# ProPrj_ftdi-jtag-xilinx_2025-01-01.net
KiCad netlist of a schematic drawn in EasyEDA Pro
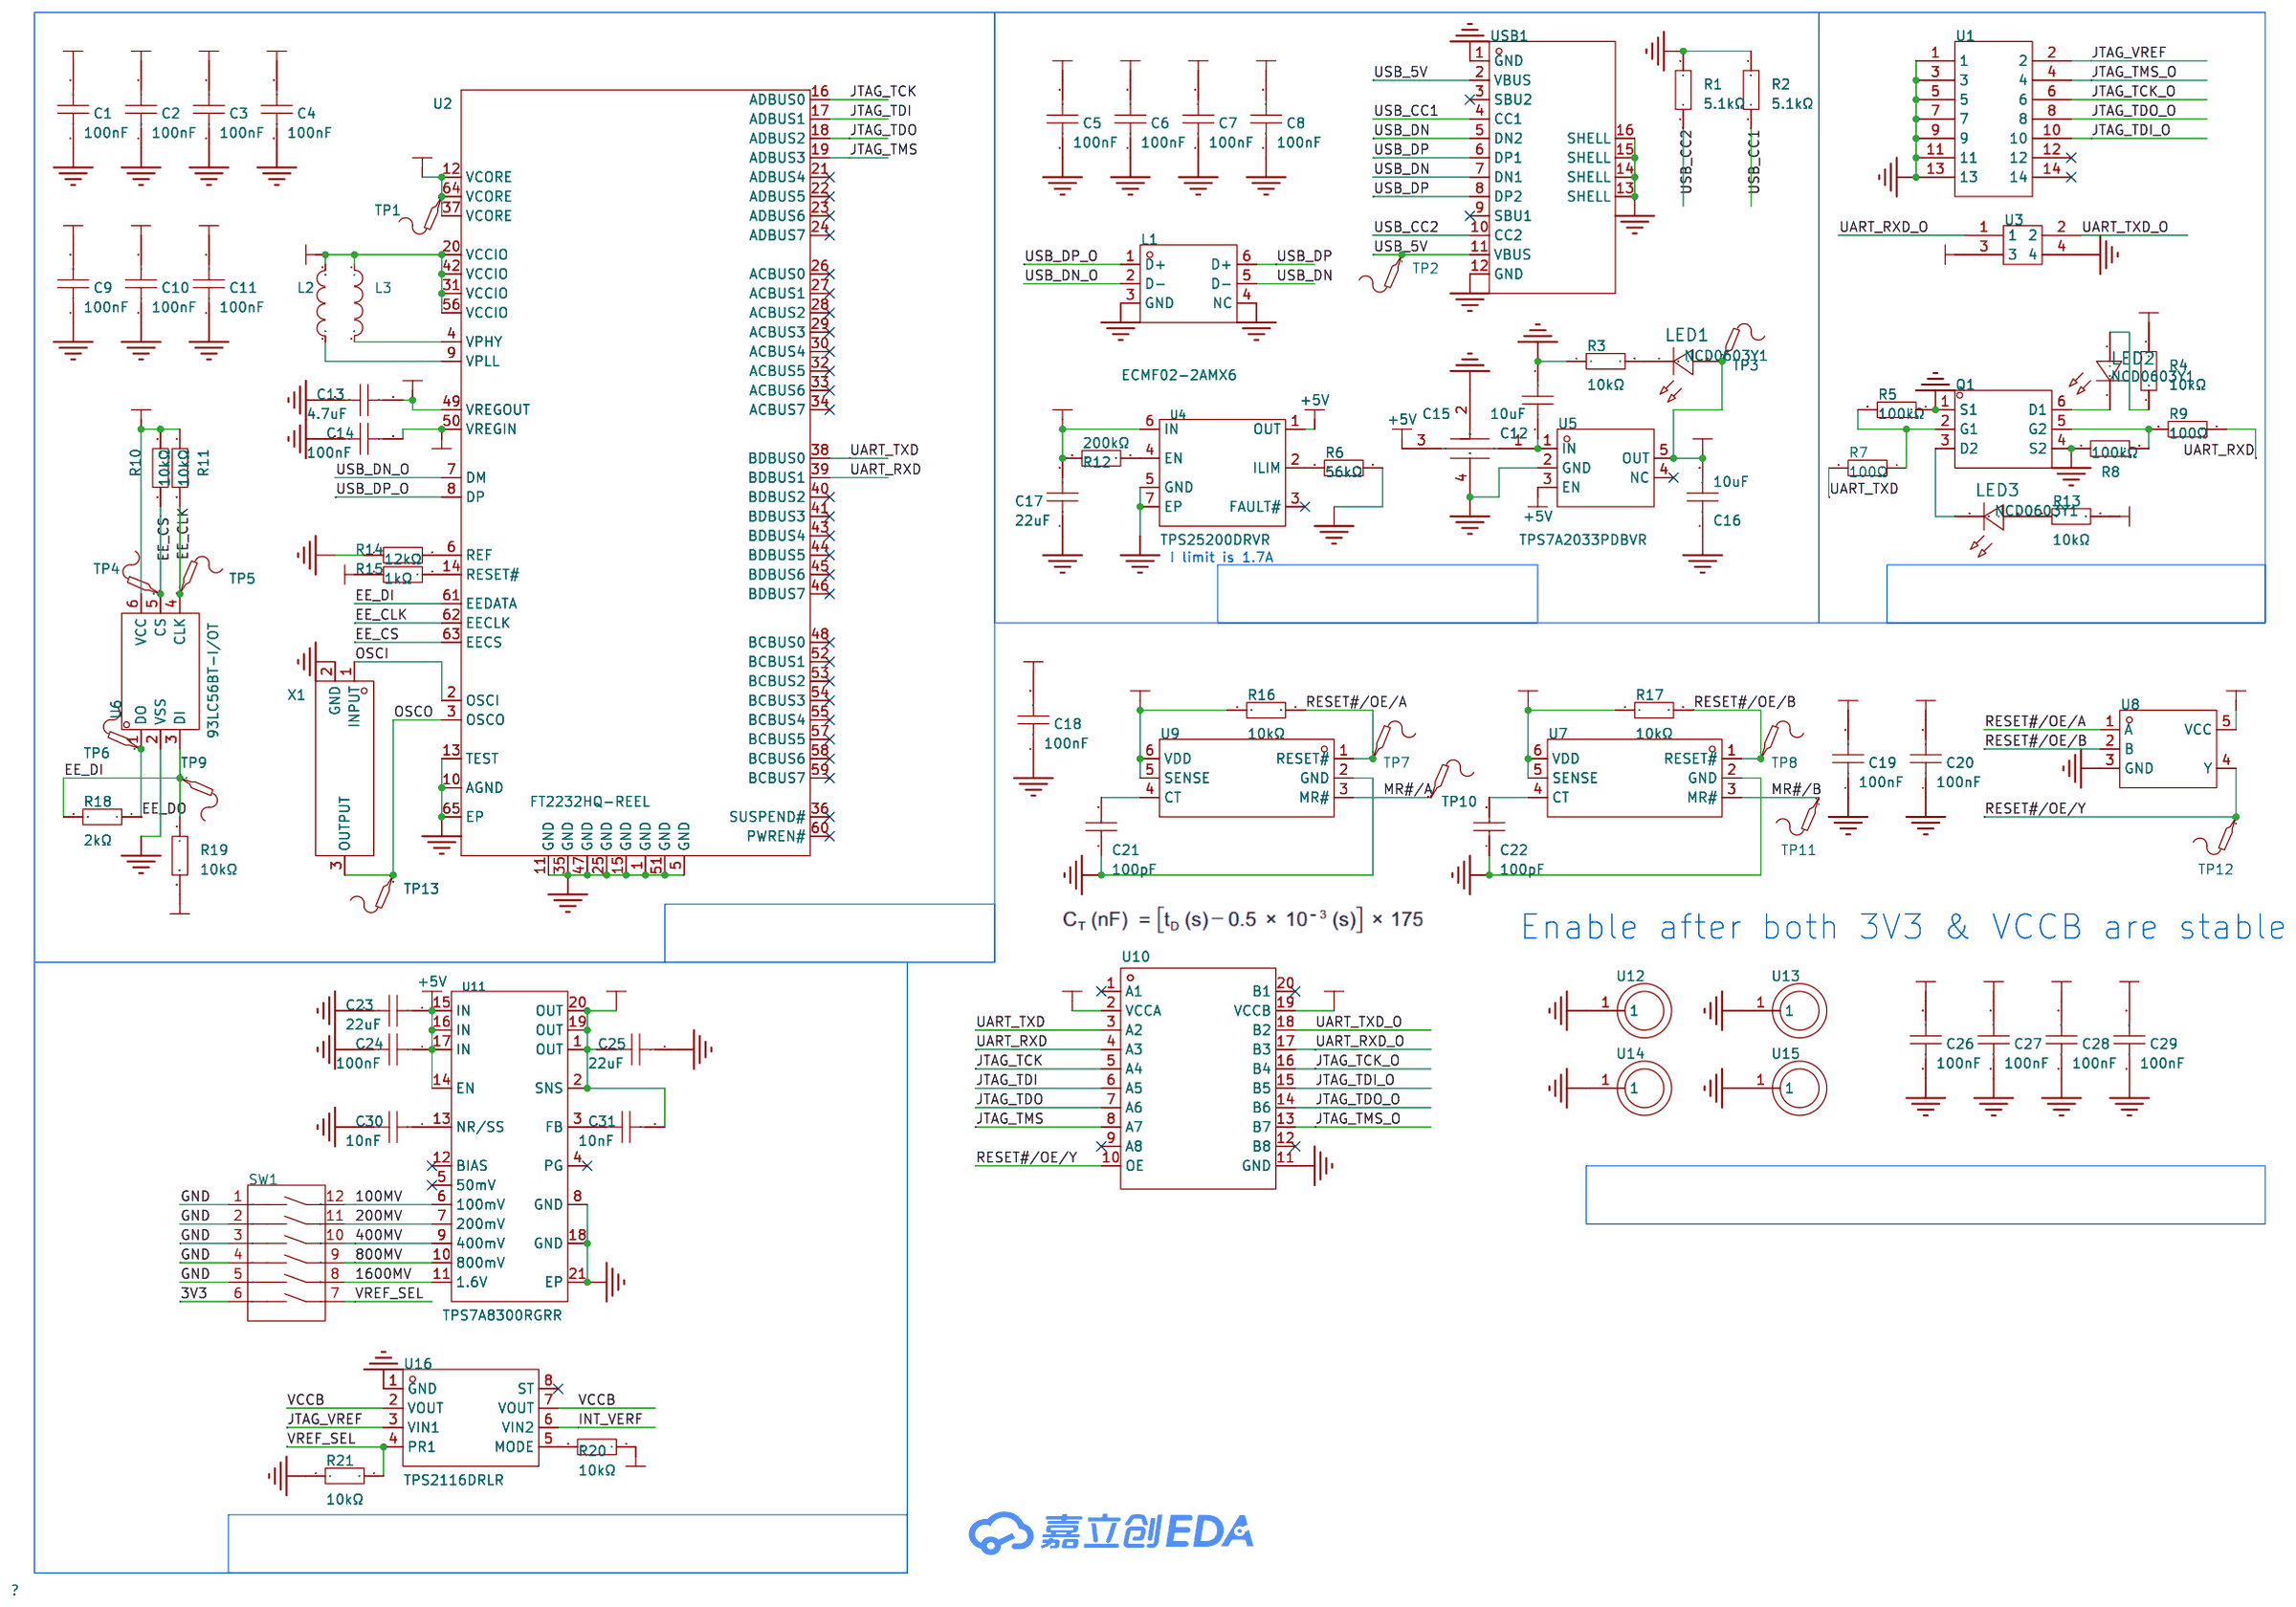
[diagram p0: FT2232HQ]
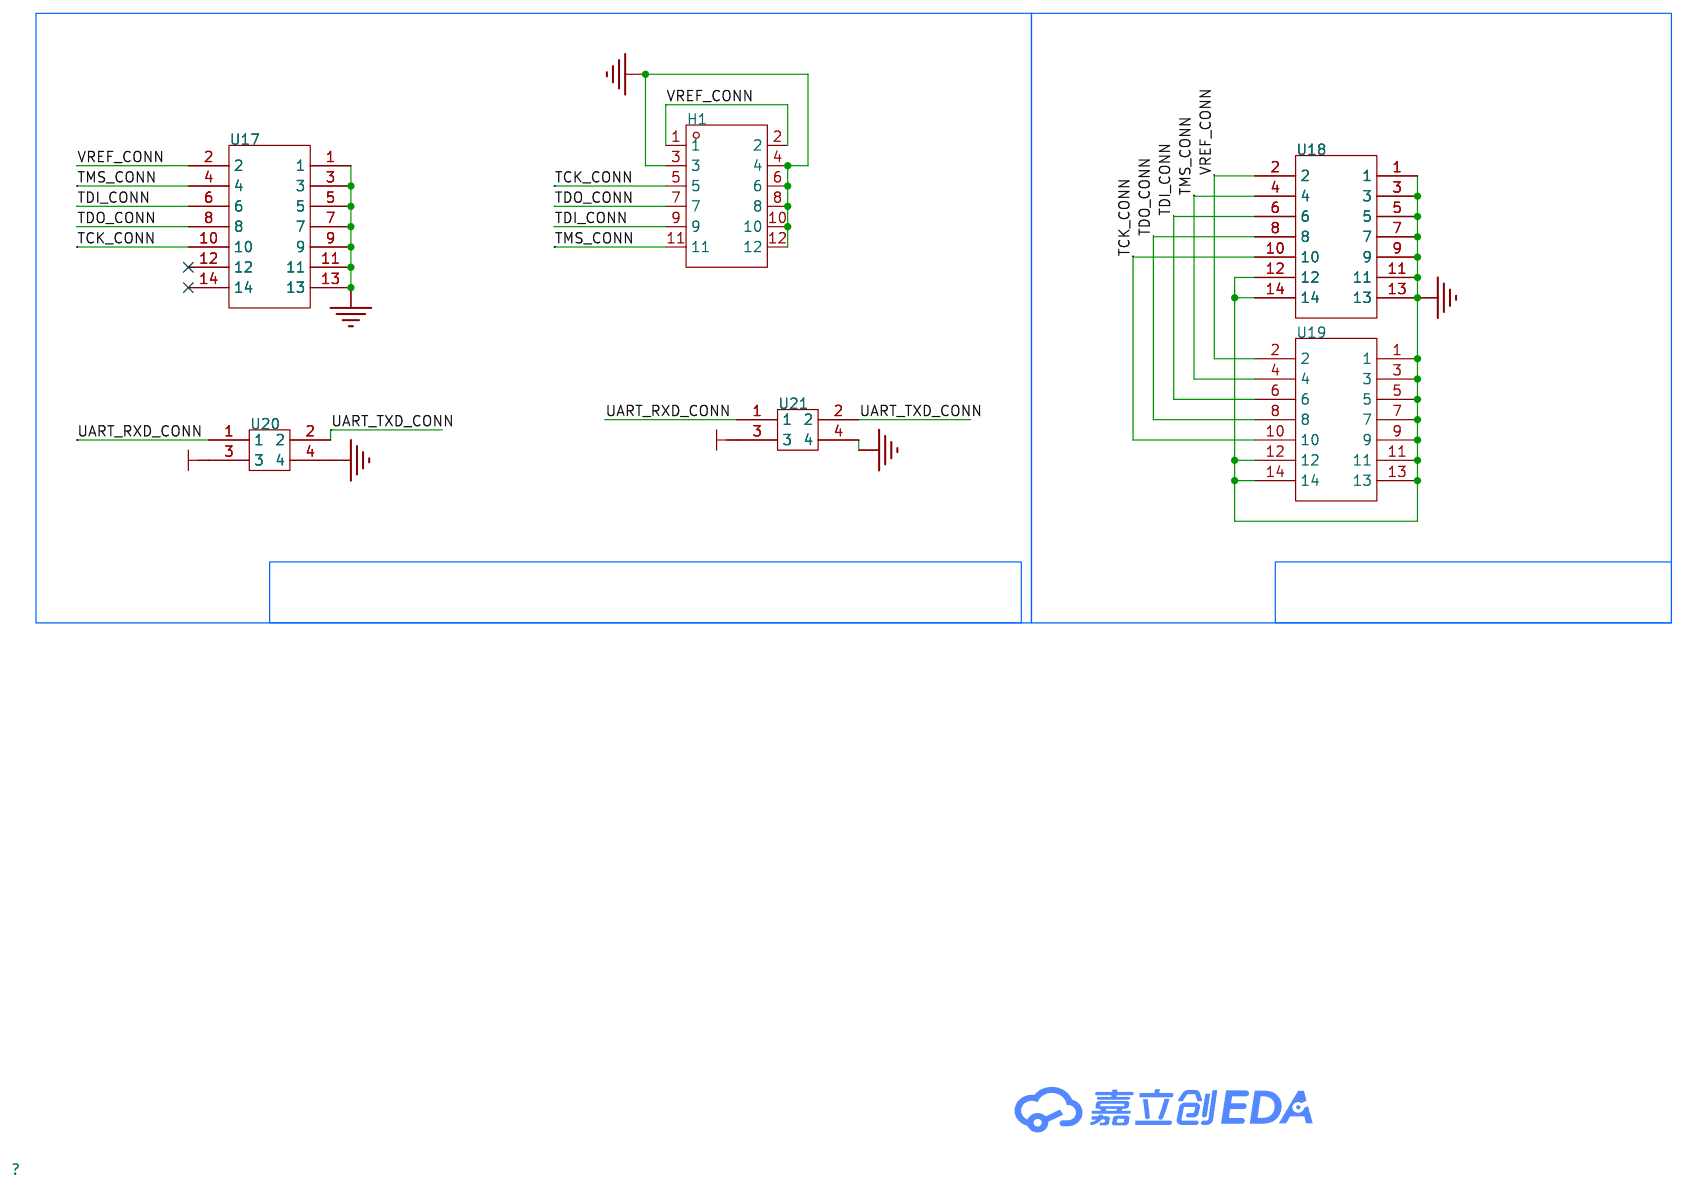
[diagram p1: JTAG Adapter]
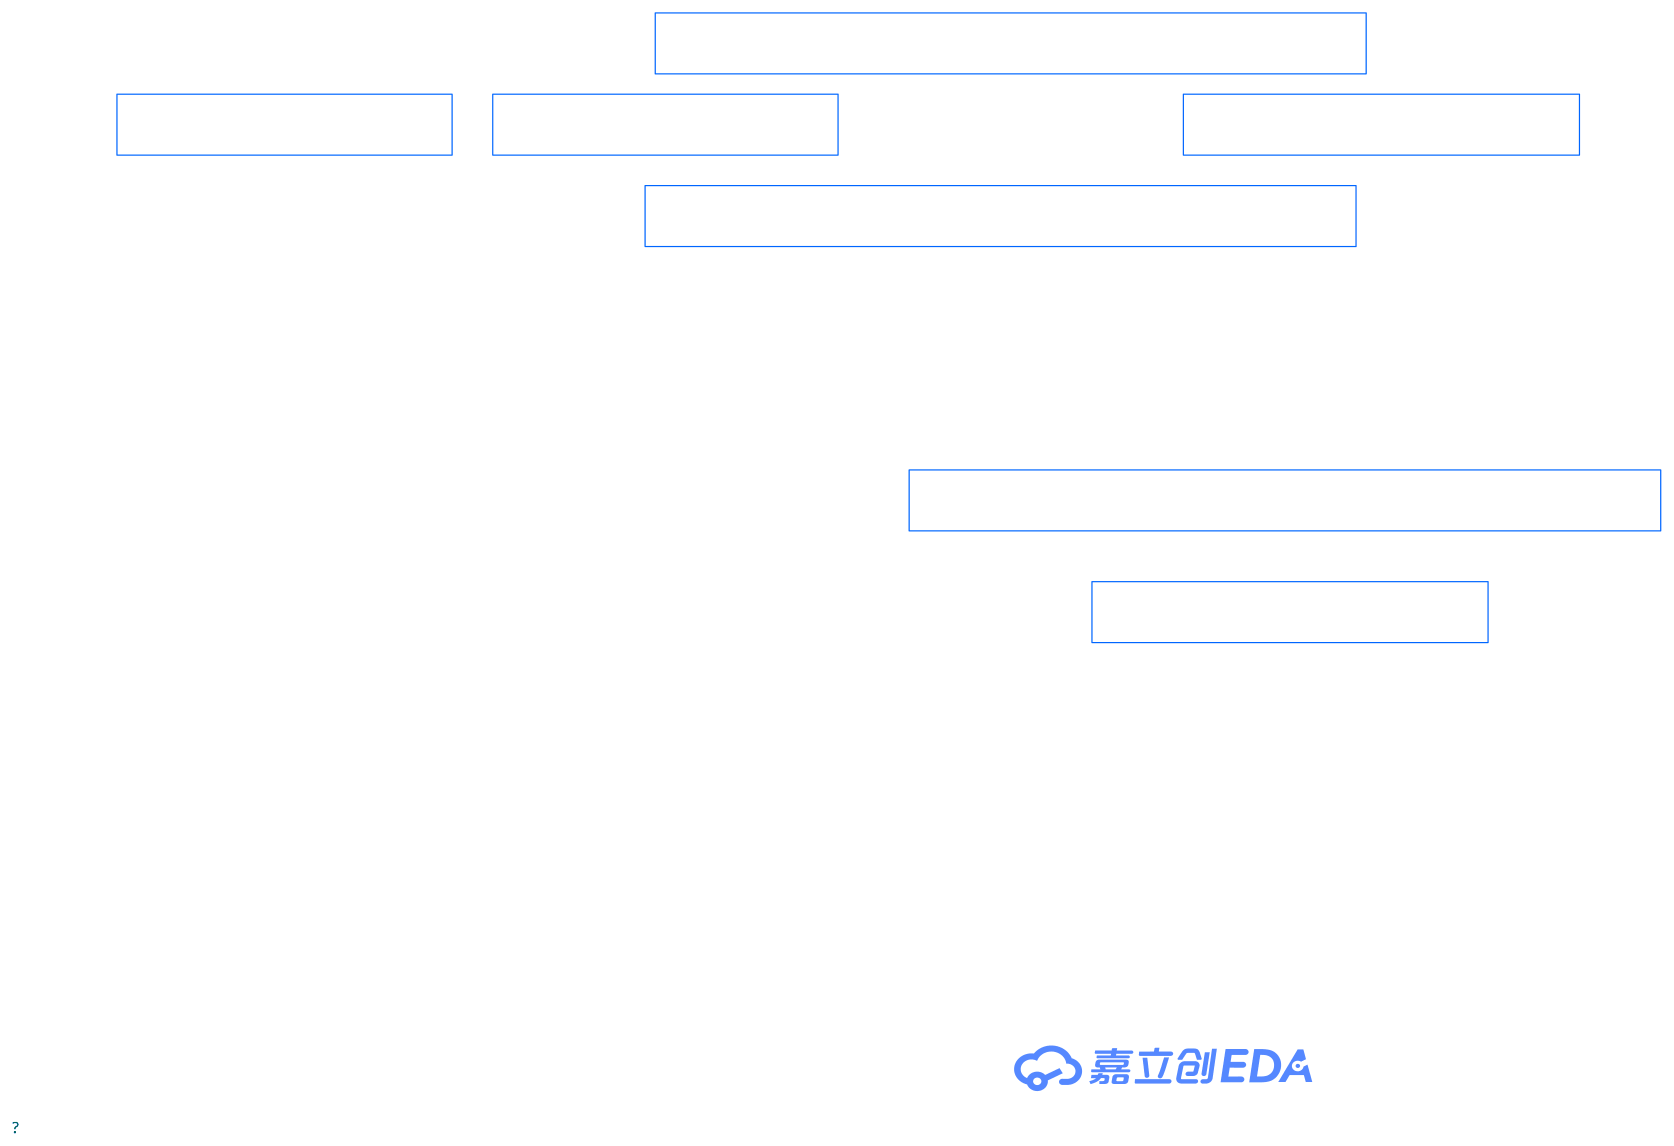
[diagram p2: Overview]

(export (version "E")
  (design (tool "Eeschema 10.0.6"))
  (components
    (comp (ref "C1")
      (value "100nF")
      (footprint "easyedapro:C0603")
      (fields
        (field (name "Manufacturer Part") "CC0402KRX7R7BB104")
        (field (name "Manufacturer") "YAGEO(国巨)")
      )
      (libsource (lib "easyedapro") (part "CapAcitance"))
    )
    (comp (ref "C2")
      (value "100nF")
      (footprint "easyedapro:C0603")
      (fields
        (field (name "Manufacturer Part") "CC0402KRX7R7BB104")
        (field (name "Manufacturer") "YAGEO(国巨)")
      )
      (libsource (lib "easyedapro") (part "CapAcitance"))
    )
    (comp (ref "C3")
      (value "100nF")
      (footprint "easyedapro:C0603")
      (fields
        (field (name "Manufacturer Part") "CC0402KRX7R7BB104")
        (field (name "Manufacturer") "YAGEO(国巨)")
      )
      (libsource (lib "easyedapro") (part "CapAcitance"))
    )
    (comp (ref "C4")
      (value "100nF")
      (footprint "easyedapro:C0603")
      (fields
        (field (name "Manufacturer Part") "CC0402KRX7R7BB104")
        (field (name "Manufacturer") "YAGEO(国巨)")
      )
      (libsource (lib "easyedapro") (part "CapAcitance"))
    )
    (comp (ref "C5")
      (value "100nF")
      (footprint "easyedapro:C0603")
      (fields
        (field (name "Manufacturer Part") "CC0402KRX7R7BB104")
        (field (name "Manufacturer") "YAGEO(国巨)")
      )
      (libsource (lib "easyedapro") (part "CapAcitance"))
    )
    (comp (ref "C6")
      (value "100nF")
      (footprint "easyedapro:C0603")
      (fields
        (field (name "Manufacturer Part") "CC0402KRX7R7BB104")
        (field (name "Manufacturer") "YAGEO(国巨)")
      )
      (libsource (lib "easyedapro") (part "CapAcitance"))
    )
    (comp (ref "C7")
      (value "100nF")
      (footprint "easyedapro:C0603")
      (fields
        (field (name "Manufacturer Part") "CC0402KRX7R7BB104")
        (field (name "Manufacturer") "YAGEO(国巨)")
      )
      (libsource (lib "easyedapro") (part "CapAcitance"))
    )
    (comp (ref "C8")
      (value "100nF")
      (footprint "easyedapro:C0603")
      (fields
        (field (name "Manufacturer Part") "CC0402KRX7R7BB104")
        (field (name "Manufacturer") "YAGEO(国巨)")
      )
      (libsource (lib "easyedapro") (part "CapAcitance"))
    )
    (comp (ref "C9")
      (value "100nF")
      (footprint "easyedapro:C0603")
      (fields
        (field (name "Manufacturer Part") "CC0402KRX7R7BB104")
        (field (name "Manufacturer") "YAGEO(国巨)")
      )
      (libsource (lib "easyedapro") (part "CapAcitance"))
    )
    (comp (ref "C10")
      (value "100nF")
      (footprint "easyedapro:C0603")
      (fields
        (field (name "Manufacturer Part") "CC0402KRX7R7BB104")
        (field (name "Manufacturer") "YAGEO(国巨)")
      )
      (libsource (lib "easyedapro") (part "CapAcitance"))
    )
    (comp (ref "C11")
      (value "100nF")
      (footprint "easyedapro:C0603")
      (fields
        (field (name "Manufacturer Part") "CC0402KRX7R7BB104")
        (field (name "Manufacturer") "YAGEO(国巨)")
      )
      (libsource (lib "easyedapro") (part "CapAcitance"))
    )
    (comp (ref "C12")
      (value "10uF")
      (footprint "easyedapro:C0603")
      (fields
        (field (name "Manufacturer Part") "CL10A106MA8NRNC")
        (field (name "Manufacturer") "SAMSUNG(三星)")
      )
      (libsource (lib "easyedapro") (part "CapAcitance"))
    )
    (comp (ref "C13")
      (value "4.7uF")
      (footprint "easyedapro:C0603")
      (fields
        (field (name "Manufacturer Part") "CL05A475KP5NRNC")
        (field (name "Manufacturer") "SAMSUNG(三星)")
      )
      (libsource (lib "easyedapro") (part "CapAcitance"))
    )
    (comp (ref "C14")
      (value "100nF")
      (footprint "easyedapro:C0603")
      (fields
        (field (name "Manufacturer Part") "CC0402KRX7R7BB104")
        (field (name "Manufacturer") "YAGEO(国巨)")
      )
      (libsource (lib "easyedapro") (part "CapAcitance"))
    )
    (comp (ref "C15")
      (value "NFM21PC104R1E3D")
      (footprint "easyedapro:CAP-SMD_4P-L2.0-W1.25")
      (description "电容量:100nF;精度:±20%;直流电阻:30mΩ;")
      (fields (field (name "Manufacturer") "muRata(村田)"))
      (libsource (lib "easyedapro") (part "NFM21PC104R1E3D"))
    )
    (comp (ref "C16")
      (value "10uF")
      (footprint "easyedapro:C0603")
      (fields
        (field (name "Manufacturer Part") "CL10A106MA8NRNC")
        (field (name "Manufacturer") "SAMSUNG(三星)")
      )
      (libsource (lib "easyedapro") (part "CapAcitance"))
    )
    (comp (ref "C17")
      (value "22uF")
      (footprint "easyedapro:C0603")
      (fields
        (field (name "Manufacturer Part") "CGA0805X5R226M350MT")
        (field (name "Manufacturer") "HRE(芯声)")
      )
      (libsource (lib "easyedapro") (part "CapAcitance"))
    )
    (comp (ref "C18")
      (value "100nF")
      (footprint "easyedapro:C0603")
      (fields
        (field (name "Manufacturer Part") "CC0402KRX7R7BB104")
        (field (name "Manufacturer") "YAGEO(国巨)")
      )
      (libsource (lib "easyedapro") (part "CapAcitance"))
    )
    (comp (ref "C19")
      (value "100nF")
      (footprint "easyedapro:C0603")
      (fields
        (field (name "Manufacturer Part") "CC0402KRX7R7BB104")
        (field (name "Manufacturer") "YAGEO(国巨)")
      )
      (libsource (lib "easyedapro") (part "CapAcitance"))
    )
    (comp (ref "C20")
      (value "100nF")
      (footprint "easyedapro:C0603")
      (fields
        (field (name "Manufacturer Part") "CC0402KRX7R7BB104")
        (field (name "Manufacturer") "YAGEO(国巨)")
      )
      (libsource (lib "easyedapro") (part "CapAcitance"))
    )
    (comp (ref "C21")
      (value "100pF")
      (footprint "easyedapro:C0402")
      (description "容值:100pF;精度:±5%;额定电压:50V;材质(温度系数):NP0;")
      (fields
        (field (name "Manufacturer Part") "CC0402JRNPO9BN101")
        (field (name "Manufacturer") "YAGEO(国巨)")
      )
      (libsource (lib "easyedapro") (part "CC0402JRNPO9BN101"))
    )
    (comp (ref "C22")
      (value "100pF")
      (footprint "easyedapro:C0402")
      (description "容值:100pF;精度:±5%;额定电压:50V;材质(温度系数):NP0;")
      (fields
        (field (name "Manufacturer Part") "CC0402JRNPO9BN101")
        (field (name "Manufacturer") "YAGEO(国巨)")
      )
      (libsource (lib "easyedapro") (part "CC0402JRNPO9BN101"))
    )
    (comp (ref "C23")
      (value "22uF")
      (footprint "easyedapro:C0603")
      (fields
        (field (name "Manufacturer Part") "CGA0805X5R226M350MT")
        (field (name "Manufacturer") "HRE(芯声)")
      )
      (libsource (lib "easyedapro") (part "CapAcitance"))
    )
    (comp (ref "C24")
      (value "100nF")
      (footprint "easyedapro:C0603")
      (fields
        (field (name "Manufacturer Part") "CC0402KRX7R7BB104")
        (field (name "Manufacturer") "YAGEO(国巨)")
      )
      (libsource (lib "easyedapro") (part "CapAcitance"))
    )
    (comp (ref "C25")
      (value "22uF")
      (footprint "easyedapro:C0603")
      (fields
        (field (name "Manufacturer Part") "CGA0805X5R226M350MT")
        (field (name "Manufacturer") "HRE(芯声)")
      )
      (libsource (lib "easyedapro") (part "CapAcitance"))
    )
    (comp (ref "C26")
      (value "100nF")
      (footprint "easyedapro:C0603")
      (fields
        (field (name "Manufacturer Part") "CC0402KRX7R7BB104")
        (field (name "Manufacturer") "YAGEO(国巨)")
      )
      (libsource (lib "easyedapro") (part "CapAcitance"))
    )
    (comp (ref "C27")
      (value "100nF")
      (footprint "easyedapro:C0603")
      (fields
        (field (name "Manufacturer Part") "CC0402KRX7R7BB104")
        (field (name "Manufacturer") "YAGEO(国巨)")
      )
      (libsource (lib "easyedapro") (part "CapAcitance"))
    )
    (comp (ref "C28")
      (value "100nF")
      (footprint "easyedapro:C0603")
      (fields
        (field (name "Manufacturer Part") "CC0402KRX7R7BB104")
        (field (name "Manufacturer") "YAGEO(国巨)")
      )
      (libsource (lib "easyedapro") (part "CapAcitance"))
    )
    (comp (ref "C29")
      (value "100nF")
      (footprint "easyedapro:C0603")
      (fields
        (field (name "Manufacturer Part") "CC0402KRX7R7BB104")
        (field (name "Manufacturer") "YAGEO(国巨)")
      )
      (libsource (lib "easyedapro") (part "CapAcitance"))
    )
    (comp (ref "C30")
      (value "10nF")
      (footprint "easyedapro:C0603")
      (fields
        (field (name "Manufacturer Part") "CC0402KRX7R9BB103")
        (field (name "Manufacturer") "YAGEO(国巨)")
      )
      (libsource (lib "easyedapro") (part "CapAcitance"))
    )
    (comp (ref "C31")
      (value "10nF")
      (footprint "easyedapro:C0603")
      (fields
        (field (name "Manufacturer Part") "CC0402KRX7R9BB103")
        (field (name "Manufacturer") "YAGEO(国巨)")
      )
      (libsource (lib "easyedapro") (part "CapAcitance"))
    )
    (comp (ref "L1")
      (value "ECMF02-2AMX6")
      (footprint "easyedapro:UFQFN-6_L1.7-W1.5")
      (description "线路数:2;直流电阻(DCR):2.5Ω;")
      (fields (field (name "Manufacturer") "ST(意法半导体)"))
      (libsource (lib "easyedapro") (part "ECMF02-2AMX6"))
    )
    (comp (ref "L2")
      (value "BLM15PD121SN1D")
      (footprint "easyedapro:L0402")
      (description "标称阻抗@测试频率:120Ω@100MHz;误差:±25%;直流电阻(RDC):90mΩ;")
      (fields (field (name "Manufacturer") "muRata(村田)"))
      (libsource (lib "easyedapro") (part "BLM15PD121SN1D"))
    )
    (comp (ref "L3")
      (value "BLM15PD121SN1D")
      (footprint "easyedapro:L0402")
      (description "标称阻抗@测试频率:120Ω@100MHz;误差:±25%;直流电阻(RDC):90mΩ;")
      (fields (field (name "Manufacturer") "muRata(村田)"))
      (libsource (lib "easyedapro") (part "BLM15PD121SN1D"))
    )
    (comp (ref "LED1")
      (value "NCD0603Y1")
      (footprint "easyedapro:LED_0603")
      (fields (field (name "Manufacturer") "国星光电"))
      (libsource (lib "easyedapro") (part "LED_R"))
    )
    (comp (ref "LED2")
      (value "NCD0603Y1")
      (footprint "easyedapro:LED_0603")
      (fields (field (name "Manufacturer") "国星光电"))
      (libsource (lib "easyedapro") (part "LED_R"))
    )
    (comp (ref "LED3")
      (value "NCD0603Y1")
      (footprint "easyedapro:LED_0603")
      (fields (field (name "Manufacturer") "国星光电"))
      (libsource (lib "easyedapro") (part "LED_R"))
    )
    (comp (ref "Q1")
      (value "BSS138PS,115")
      (footprint "easyedapro:SOT-363_L2.0-W1.3-P0.65-LS2.1-BR")
      (fields (field (name "Manufacturer") "Nexperia(安世)"))
      (libsource (lib "easyedapro") (part "BSS138PS,115"))
    )
    (comp (ref "R1")
      (value "5.1kΩ")
      (footprint "easyedapro:R0603")
      (fields
        (field (name "Manufacturer Part") "0402WGF5101TCE")
        (field (name "Manufacturer") "UNI-ROYAL(厚声)")
      )
      (libsource (lib "easyedapro") (part "电阻"))
    )
    (comp (ref "R2")
      (value "5.1kΩ")
      (footprint "easyedapro:R0603")
      (fields
        (field (name "Manufacturer Part") "0402WGF5101TCE")
        (field (name "Manufacturer") "UNI-ROYAL(厚声)")
      )
      (libsource (lib "easyedapro") (part "电阻"))
    )
    (comp (ref "R3")
      (value "10kΩ")
      (footprint "easyedapro:R0603")
      (fields (field (name "Manufacturer Part") "RC0402FR-0710KL") (field (name "Manufacturer") "YAGEO(国巨)"))
      (libsource (lib "easyedapro") (part "电阻"))
    )
    (comp (ref "R4")
      (value "10kΩ")
      (footprint "easyedapro:R0603")
      (fields (field (name "Manufacturer Part") "RC0402FR-0710KL") (field (name "Manufacturer") "YAGEO(国巨)"))
      (libsource (lib "easyedapro") (part "电阻"))
    )
    (comp (ref "R5")
      (value "100kΩ")
      (footprint "easyedapro:R0603")
      (fields (field (name "Manufacturer Part") "RC0402FR-07100KL") (field (name "Manufacturer") "YAGEO(国巨)"))
      (libsource (lib "easyedapro") (part "电阻"))
    )
    (comp (ref "R6")
      (value "56kΩ")
      (footprint "easyedapro:R0603")
      (fields
        (field (name "Manufacturer Part") "0402WGF5602TCE")
        (field (name "Manufacturer") "UNI-ROYAL(厚声)")
      )
      (libsource (lib "easyedapro") (part "电阻"))
    )
    (comp (ref "R7")
      (value "100Ω")
      (footprint "easyedapro:R0603")
      (fields
        (field (name "Manufacturer Part") "0402WGF1000TCE")
        (field (name "Manufacturer") "UNI-ROYAL(厚声)")
      )
      (libsource (lib "easyedapro") (part "电阻"))
    )
    (comp (ref "R8")
      (value "100kΩ")
      (footprint "easyedapro:R0603")
      (fields (field (name "Manufacturer Part") "RC0402FR-07100KL") (field (name "Manufacturer") "YAGEO(国巨)"))
      (libsource (lib "easyedapro") (part "电阻"))
    )
    (comp (ref "R9")
      (value "100Ω")
      (footprint "easyedapro:R0603")
      (fields
        (field (name "Manufacturer Part") "0402WGF1000TCE")
        (field (name "Manufacturer") "UNI-ROYAL(厚声)")
      )
      (libsource (lib "easyedapro") (part "电阻"))
    )
    (comp (ref "R10")
      (value "10kΩ")
      (footprint "easyedapro:R0603")
      (fields (field (name "Manufacturer Part") "RC0402FR-0710KL") (field (name "Manufacturer") "YAGEO(国巨)"))
      (libsource (lib "easyedapro") (part "电阻"))
    )
    (comp (ref "R11")
      (value "10kΩ")
      (footprint "easyedapro:R0603")
      (fields (field (name "Manufacturer Part") "RC0402FR-0710KL") (field (name "Manufacturer") "YAGEO(国巨)"))
      (libsource (lib "easyedapro") (part "电阻"))
    )
    (comp (ref "R12")
      (value "200kΩ")
      (footprint "easyedapro:R0603")
      (fields
        (field (name "Manufacturer Part") "0402WGF2003TCE")
        (field (name "Manufacturer") "UNI-ROYAL(厚声)")
      )
      (libsource (lib "easyedapro") (part "电阻"))
    )
    (comp (ref "R13")
      (value "10kΩ")
      (footprint "easyedapro:R0603")
      (fields (field (name "Manufacturer Part") "RC0402FR-0710KL") (field (name "Manufacturer") "YAGEO(国巨)"))
      (libsource (lib "easyedapro") (part "电阻"))
    )
    (comp (ref "R14")
      (value "12kΩ")
      (footprint "easyedapro:R0603")
      (fields
        (field (name "Manufacturer Part") "0402WGF1202TCE")
        (field (name "Manufacturer") "UNI-ROYAL(厚声)")
      )
      (libsource (lib "easyedapro") (part "电阻"))
    )
    (comp (ref "R15")
      (value "1kΩ")
      (footprint "easyedapro:R0603")
      (fields
        (field (name "Manufacturer Part") "0402WGF1001TCE")
        (field (name "Manufacturer") "UNI-ROYAL(厚声)")
      )
      (libsource (lib "easyedapro") (part "电阻"))
    )
    (comp (ref "R16")
      (value "10kΩ")
      (footprint "easyedapro:R0603")
      (fields (field (name "Manufacturer Part") "RC0402FR-0710KL") (field (name "Manufacturer") "YAGEO(国巨)"))
      (libsource (lib "easyedapro") (part "电阻"))
    )
    (comp (ref "R17")
      (value "10kΩ")
      (footprint "easyedapro:R0603")
      (fields (field (name "Manufacturer Part") "RC0402FR-0710KL") (field (name "Manufacturer") "YAGEO(国巨)"))
      (libsource (lib "easyedapro") (part "电阻"))
    )
    (comp (ref "R18")
      (value "2kΩ")
      (footprint "easyedapro:R0603")
      (fields (field (name "Manufacturer Part") "FRC0402F2001TS") (field (name "Manufacturer") "FOJAN(富捷)"))
      (libsource (lib "easyedapro") (part "电阻"))
    )
    (comp (ref "R19")
      (value "10kΩ")
      (footprint "easyedapro:R0603")
      (fields (field (name "Manufacturer Part") "RC0402FR-0710KL") (field (name "Manufacturer") "YAGEO(国巨)"))
      (libsource (lib "easyedapro") (part "电阻"))
    )
    (comp (ref "R20")
      (value "10kΩ")
      (footprint "easyedapro:R0603")
      (fields (field (name "Manufacturer Part") "RC0402FR-0710KL") (field (name "Manufacturer") "YAGEO(国巨)"))
      (libsource (lib "easyedapro") (part "电阻"))
    )
    (comp (ref "R21")
      (value "10kΩ")
      (footprint "easyedapro:R0603")
      (fields (field (name "Manufacturer Part") "RC0402FR-0710KL") (field (name "Manufacturer") "YAGEO(国巨)"))
      (libsource (lib "easyedapro") (part "电阻"))
    )
    (comp (ref "SW1")
      (value "SMQP-06B-TP")
      (footprint "easyedapro:SW-TH_12P-P2.54_SMQP-06B-TP")
      (description "类型:琴键;电路结构:-;开关位数:6位;额定电流:25mA;额定电压:24V;使用寿命:5千次;颜色:蓝色;")
      (fields (field (name "Manufacturer") "SM Switch"))
      (libsource (lib "easyedapro") (part "SMQP-06B-TP"))
    )
    (comp (ref "TP1")
      (value "~")
      (footprint "easyedapro:Test-Point-0.5mm")
      (description "Test Point 测试点")
      (libsource (lib "easyedapro") (part "Test-Point"))
    )
    (comp (ref "TP2")
      (value "~")
      (footprint "easyedapro:Test-Point-0.5mm")
      (description "Test Point 测试点")
      (libsource (lib "easyedapro") (part "Test-Point"))
    )
    (comp (ref "TP3")
      (value "~")
      (footprint "easyedapro:Test-Point-0.5mm")
      (description "Test Point 测试点")
      (libsource (lib "easyedapro") (part "Test-Point"))
    )
    (comp (ref "TP4")
      (value "~")
      (footprint "easyedapro:Test-Point-0.5mm")
      (description "Test Point 测试点")
      (libsource (lib "easyedapro") (part "Test-Point"))
    )
    (comp (ref "TP5")
      (value "~")
      (footprint "easyedapro:Test-Point-0.5mm")
      (description "Test Point 测试点")
      (libsource (lib "easyedapro") (part "Test-Point"))
    )
    (comp (ref "TP6")
      (value "~")
      (footprint "easyedapro:Test-Point-0.5mm")
      (description "Test Point 测试点")
      (libsource (lib "easyedapro") (part "Test-Point"))
    )
    (comp (ref "TP7")
      (value "~")
      (footprint "easyedapro:Test-Point-0.5mm")
      (description "Test Point 测试点")
      (libsource (lib "easyedapro") (part "Test-Point"))
    )
    (comp (ref "TP8")
      (value "~")
      (footprint "easyedapro:Test-Point-0.5mm")
      (description "Test Point 测试点")
      (libsource (lib "easyedapro") (part "Test-Point"))
    )
    (comp (ref "TP9")
      (value "~")
      (footprint "easyedapro:Test-Point-0.5mm")
      (description "Test Point 测试点")
      (libsource (lib "easyedapro") (part "Test-Point"))
    )
    (comp (ref "TP10")
      (value "~")
      (footprint "easyedapro:Test-Point-0.5mm")
      (description "Test Point 测试点")
      (libsource (lib "easyedapro") (part "Test-Point"))
    )
    (comp (ref "TP11")
      (value "~")
      (footprint "easyedapro:Test-Point-0.5mm")
      (description "Test Point 测试点")
      (libsource (lib "easyedapro") (part "Test-Point"))
    )
    (comp (ref "TP12")
      (value "~")
      (footprint "easyedapro:Test-Point-0.5mm")
      (description "Test Point 测试点")
      (libsource (lib "easyedapro") (part "Test-Point"))
    )
    (comp (ref "TP13")
      (value "~")
      (footprint "easyedapro:Test-Point-0.5mm")
      (description "Test Point 测试点")
      (libsource (lib "easyedapro") (part "Test-Point"))
    )
    (comp (ref "U1")
      (value "~")
      (footprint "easyedapro:JTAG_V3")
      (libsource (lib "easyedapro") (part "jtagv4"))
    )
    (comp (ref "U2")
      (value "FT2232HQ-REEL")
      (footprint "easyedapro:QFN-64_L9.0-W9.0-P0.50-TL-EP4.3")
      (description "应用功能:USB转UART；USB转FIFO;接口协议:UART;供电电压:3V~3.6V;")
      (fields (field (name "Manufacturer") "FTDI(飞特帝亚)"))
      (libsource (lib "easyedapro") (part "FT2232HQ-REEL"))
    )
    (comp (ref "U3") (value "~") (footprint "easyedapro:2x2p侧贴排针") (libsource (lib "easyedapro") (part "2")))
    (comp (ref "U4")
      (value "TPS25200DRVR")
      (footprint "easyedapro:WSON-6_L2.0-W2.0-P0.65-TL-EP")
      (description "TPS25200 具有过压钳位的 6.5V/2.8A 电子保险丝")
      (fields (field (name "Manufacturer") "TI(德州仪器)"))
      (libsource (lib "easyedapro") (part "TPS25200DRVR"))
    )
    (comp (ref "U5")
      (value "TPS7A2033PDBVR")
      (footprint "easyedapro:SOT-23-5_L2.9-W1.6-P0.95-LS2.8-BR")
      (fields (field (name "Manufacturer") "TI(德州仪器)"))
      (libsource (lib "easyedapro") (part "TPS7A2033PDBVR"))
    )
    (comp (ref "U6")
      (value "93LC56BT-I/OT")
      (footprint "easyedapro:SOT-23-6_L2.9-W1.6-P0.95-LS2.8-BR")
      (fields (field (name "Manufacturer") "MICROCHIP(美国微芯)"))
      (libsource (lib "easyedapro") (part "93LC56BT-I/OT"))
    )
    (comp (ref "U7")
      (value "TPS3808G33DBVR")
      (footprint "easyedapro:SOT-23-6_L2.9-W1.6-P0.95-LS2.8-BR")
      (description "复位有效电平:低电平有效;受监控电压数:1;复位超时:-;")
      (fields (field (name "Manufacturer") "TI(德州仪器)"))
      (libsource (lib "easyedapro") (part "TPS3808G33DBVR"))
    )
    (comp (ref "U8")
      (value "SN74LVC1G08DBVR")
      (footprint "easyedapro:TSOT-23-5_L2.9-W1.6-P0.95-LS2.8-BR")
      (description "逻辑类型:与门;通道数:1;电源电压:1.65V~5.5V;静态电流(最大值):10uA;最大传播延迟:10ns@5V,15pF;")
      (fields (field (name "Manufacturer") "UMW(友台半导体)"))
      (libsource (lib "easyedapro") (part "SN74LVC1G08DBVR_C434068"))
    )
    (comp (ref "U9")
      (value "TPS3808G33DBVR")
      (footprint "easyedapro:SOT-23-6_L2.9-W1.6-P0.95-LS2.8-BR")
      (description "复位有效电平:低电平有效;受监控电压数:1;复位超时:-;")
      (fields (field (name "Manufacturer") "TI(德州仪器)"))
      (libsource (lib "easyedapro") (part "TPS3808G33DBVR"))
    )
    (comp (ref "U10")
      (value "TXB0108PWR")
      (footprint "easyedapro:TSSOP-20_L6.5-W4.4-P0.65-LS6.4-BL")
      (description "数据速率:100Mbps;电压(VCCA):1.2V~3.6V;电压(VCCB):1.65V~5.5V;电路数:1;每个电路通道数:8;")
      (fields (field (name "Manufacturer") "TI(德州仪器)"))
      (libsource (lib "easyedapro") (part "TXB0108PWR"))
    )
    (comp (ref "U11")
      (value "TPS7A8300RGRR")
      (footprint "easyedapro:VQFN-20_L3.5-W3.5-P0.50-BL-EP2.0")
      (description "输出类型:-;")
      (fields (field (name "Manufacturer") "TI(德州仪器)"))
      (libsource (lib "easyedapro") (part "TPS7A8300RGRR"))
    )
    (comp (ref "U12")
      (value "~")
      (footprint "easyedapro:M2焊接螺柱")
      (libsource (lib "easyedapro") (part "M2焊接螺柱"))
    )
    (comp (ref "U13")
      (value "~")
      (footprint "easyedapro:M2焊接螺柱")
      (libsource (lib "easyedapro") (part "M2焊接螺柱"))
    )
    (comp (ref "U14")
      (value "~")
      (footprint "easyedapro:M2焊接螺柱")
      (libsource (lib "easyedapro") (part "M2焊接螺柱"))
    )
    (comp (ref "U15")
      (value "~")
      (footprint "easyedapro:M2焊接螺柱")
      (libsource (lib "easyedapro") (part "M2焊接螺柱"))
    )
    (comp (ref "U16")
      (value "TPS2116DRLR")
      (footprint "easyedapro:SOT-583-8_L2.1-W1.6-P0.50-LS1.6-BL")
      (description "通道数:1;输出电流:2.5A;输入电压:1.6V~5.5V;导通电阻:42mΩ;")
      (fields (field (name "Manufacturer") "TI(德州仪器)"))
      (libsource (lib "easyedapro") (part "TPS2116DRLR"))
    )
    (comp (ref "USB1")
      (value "TYPEC-302-BRP16SC16")
      (footprint "easyedapro:USB-C-SMD_TYPEC-302-BRP16SC16")
      (fields (field (name "Manufacturer") "XUNPU(讯普)"))
      (libsource (lib "easyedapro") (part "TYPEC-302-BRP16SC16"))
    )
    (comp (ref "X1")
      (value "12MHz")
      (footprint "easyedapro:CRYSTAL-SMD_3P-L3.2-W1.3-P1.2-BL")
      (description "频率:12MHz;内置负载电容:10pF;谐振阻抗:30Ω;")
      (fields
        (field (name "Manufacturer Part") "CSTNE12M0G52A000R0")
        (field (name "Manufacturer") "muRata(村田)")
      )
      (libsource (lib "easyedapro") (part "CSTNE12M0G52A000R0"))
    )
    (comp (ref "H1")
      (value "PZ2.54-2x6-11.2")
      (footprint "easyedapro:HDR-TH_12P-P2.54-V-M-R2-C6-S2.54")
      (fields (field (name "Manufacturer") "ZHOURI(洲日)"))
      (libsource (lib "easyedapro") (part "PZ2.54-2X6-11.2"))
    )
    (comp (ref "U17")
      (value "~")
      (footprint "easyedapro:JTAG_V3")
      (libsource (lib "easyedapro") (part "jtagv4"))
    )
    (comp (ref "U18")
      (value "~")
      (footprint "easyedapro:JTAG_V3")
      (libsource (lib "easyedapro") (part "jtagv4"))
    )
    (comp (ref "U19")
      (value "~")
      (footprint "easyedapro:JTAG_V3")
      (libsource (lib "easyedapro") (part "jtagv4"))
    )
    (comp (ref "U20") (value "~") (footprint "easyedapro:2x2p侧贴排针") (libsource (lib "easyedapro") (part "2")))
    (comp (ref "U21") (value "~") (footprint "easyedapro:2x2p侧贴排针") (libsource (lib "easyedapro") (part "2")))
  )
  (nets
    (net (code "1") (name "+5V") (class "Default")
      (node (ref "C15") (pin "3") (pinfunction "OUT_3") (pintype "input"))
      (node (ref "C23") (pin "2") (pinfunction "2_2") (pintype "input"))
      (node (ref "C24") (pin "1") (pinfunction "1_1") (pintype "input"))
      (node (ref "U11") (pin "14") (pinfunction "EN_14") (pintype "input"))
      (node (ref "U11") (pin "15") (pinfunction "IN_15") (pintype "input"))
      (node (ref "U11") (pin "16") (pinfunction "IN_16") (pintype "input"))
      (node (ref "U11") (pin "17") (pinfunction "IN_17") (pintype "input"))
      (node (ref "U4") (pin "1") (pinfunction "OUT_1") (pintype "input"))
      (node (ref "U5") (pin "3") (pinfunction "EN_3") (pintype "input"))
    )
    (net (code "2") (name "3V3") (class "Default")
      (node (ref "C1") (pin "2") (pinfunction "2_2") (pintype "input"))
      (node (ref "C14") (pin "2") (pinfunction "2_2") (pintype "input"))
      (node (ref "C16") (pin "2") (pinfunction "2_2") (pintype "input"))
      (node (ref "C18") (pin "2") (pinfunction "2_2") (pintype "input"))
      (node (ref "C2") (pin "2") (pinfunction "2_2") (pintype "input"))
      (node (ref "C20") (pin "2") (pinfunction "2_2") (pintype "input"))
      (node (ref "C26") (pin "2") (pinfunction "2_2") (pintype "input"))
      (node (ref "C27") (pin "2") (pinfunction "2_2") (pintype "input"))
      (node (ref "C3") (pin "2") (pinfunction "2_2") (pintype "input"))
      (node (ref "C4") (pin "2") (pinfunction "2_2") (pintype "input"))
      (node (ref "C5") (pin "2") (pinfunction "2_2") (pintype "input"))
      (node (ref "C6") (pin "2") (pinfunction "2_2") (pintype "input"))
      (node (ref "C7") (pin "2") (pinfunction "2_2") (pintype "input"))
      (node (ref "C8") (pin "2") (pinfunction "2_2") (pintype "input"))
      (node (ref "L2") (pin "2") (pinfunction "2_2") (pintype "input"))
      (node (ref "L3") (pin "1") (pinfunction "1_1") (pintype "input"))
      (node (ref "LED1") (pin "2") (pinfunction "A_2") (pintype "input"))
      (node (ref "R10") (pin "1") (pinfunction "1_1") (pintype "input"))
      (node (ref "R11") (pin "1") (pinfunction "1_1") (pintype "input"))
      (node (ref "R13") (pin "1") (pinfunction "1_1") (pintype "input"))
      (node (ref "R15") (pin "1") (pinfunction "1_1") (pintype "input"))
      (node (ref "R16") (pin "1") (pinfunction "1_1") (pintype "input"))
      (node (ref "R19") (pin "2") (pinfunction "2_2") (pintype "input"))
      (node (ref "R20") (pin "1") (pinfunction "1_1") (pintype "input"))
      (node (ref "R4") (pin "2") (pinfunction "2_2") (pintype "input"))
      (node (ref "SW1") (pin "6") (pinfunction "6_6") (pintype "unspecified"))
      (node (ref "TP3") (pin "1") (pinfunction "1_1") (pintype "input"))
      (node (ref "U10") (pin "2") (pinfunction "VCCA_2") (pintype "unspecified"))
      (node (ref "U2") (pin "20") (pinfunction "VCCIO_20") (pintype "input"))
      (node (ref "U2") (pin "31") (pinfunction "VCCIO_31") (pintype "input"))
      (node (ref "U2") (pin "42") (pinfunction "VCCIO_42") (pintype "input"))
      (node (ref "U2") (pin "50") (pinfunction "VREGIN_50") (pintype "input"))
      (node (ref "U2") (pin "56") (pinfunction "VCCIO_56") (pintype "input"))
      (node (ref "U3") (pin "3") (pinfunction "3_3") (pintype "input"))
      (node (ref "U5") (pin "5") (pinfunction "OUT_5") (pintype "input"))
      (node (ref "U6") (pin "6") (pinfunction "VCC_6") (pintype "input"))
      (node (ref "U8") (pin "5") (pinfunction "VCC_5") (pintype "unspecified"))
      (node (ref "U9") (pin "5") (pinfunction "SENSE_5") (pintype "unspecified"))
      (node (ref "U9") (pin "6") (pinfunction "VDD_6") (pintype "unspecified"))
    )
    (net (code "3") (name "3V3_CONN") (class "Default")
      (node (ref "U20") (pin "3") (pinfunction "3_3") (pintype "input"))
      (node (ref "U21") (pin "3") (pinfunction "3_3") (pintype "input"))
    )
    (net (code "4") (name "100MV") (class "Default")
      (node (ref "SW1") (pin "12") (pinfunction "12_12") (pintype "unspecified"))
      (node (ref "U11") (pin "6") (pinfunction "100mV_6") (pintype "input"))
    )
    (net (code "5") (name "200MV") (class "Default")
      (node (ref "SW1") (pin "11") (pinfunction "11_11") (pintype "unspecified"))
      (node (ref "U11") (pin "7") (pinfunction "200mV_7") (pintype "input"))
    )
    (net (code "6") (name "400MV") (class "Default")
      (node (ref "SW1") (pin "10") (pinfunction "10_10") (pintype "unspecified"))
      (node (ref "U11") (pin "9") (pinfunction "400mV_9") (pintype "input"))
    )
    (net (code "7") (name "800MV") (class "Default")
      (node (ref "SW1") (pin "9") (pinfunction "9_9") (pintype "unspecified"))
      (node (ref "U11") (pin "10") (pinfunction "800mV_10") (pintype "input"))
    )
    (net (code "8") (name "1600MV") (class "Default")
      (node (ref "SW1") (pin "8") (pinfunction "8_8") (pintype "unspecified"))
      (node (ref "U11") (pin "11") (pinfunction "1.6V_11") (pintype "input"))
    )
    (net (code "9") (name "EE_CLK") (class "Default")
      (node (ref "R11") (pin "2") (pinfunction "2_2") (pintype "input"))
      (node (ref "TP5") (pin "1") (pinfunction "1_1") (pintype "input"))
      (node (ref "U2") (pin "62") (pinfunction "EECLK_62") (pintype "input"))
      (node (ref "U6") (pin "4") (pinfunction "CLK_4") (pintype "input"))
    )
    (net (code "10") (name "EE_CS") (class "Default")
      (node (ref "R10") (pin "2") (pinfunction "2_2") (pintype "input"))
      (node (ref "TP4") (pin "1") (pinfunction "1_1") (pintype "input"))
      (node (ref "U2") (pin "63") (pinfunction "EECS_63") (pintype "input"))
      (node (ref "U6") (pin "5") (pinfunction "CS_5") (pintype "input"))
    )
    (net (code "11") (name "EE_DI") (class "Default")
      (node (ref "R18") (pin "2") (pinfunction "2_2") (pintype "input"))
      (node (ref "R19") (pin "1") (pinfunction "1_1") (pintype "input"))
      (node (ref "TP9") (pin "1") (pinfunction "1_1") (pintype "input"))
      (node (ref "U2") (pin "61") (pinfunction "EEDATA_61") (pintype "input"))
      (node (ref "U6") (pin "3") (pinfunction "DI_3") (pintype "input"))
    )
    (net (code "12") (name "EE_DO") (class "Default")
      (node (ref "R18") (pin "1") (pinfunction "1_1") (pintype "input"))
      (node (ref "TP6") (pin "1") (pinfunction "1_1") (pintype "input"))
      (node (ref "U6") (pin "1") (pinfunction "DO_1") (pintype "input"))
    )
    (net (code "13") (name "GND") (class "Default")
      (node (ref "C1") (pin "1") (pinfunction "1_1") (pintype "input"))
      (node (ref "C10") (pin "1") (pinfunction "1_1") (pintype "input"))
      (node (ref "C11") (pin "1") (pinfunction "1_1") (pintype "input"))
      (node (ref "C12") (pin "2") (pinfunction "2_2") (pintype "input"))
      (node (ref "C13") (pin "2") (pinfunction "2_2") (pintype "input"))
      (node (ref "C14") (pin "1") (pinfunction "1_1") (pintype "input"))
      (node (ref "C15") (pin "2") (pinfunction "GND_2") (pintype "input"))
      (node (ref "C15") (pin "4") (pinfunction "GND_4") (pintype "input"))
      (node (ref "C16") (pin "1") (pinfunction "1_1") (pintype "input"))
      (node (ref "C17") (pin "1") (pinfunction "1_1") (pintype "input"))
      (node (ref "C18") (pin "1") (pinfunction "1_1") (pintype "input"))
      (node (ref "C19") (pin "1") (pinfunction "1_1") (pintype "input"))
      (node (ref "C2") (pin "1") (pinfunction "1_1") (pintype "input"))
      (node (ref "C20") (pin "1") (pinfunction "1_1") (pintype "input"))
      (node (ref "C21") (pin "1") (pinfunction "1_1") (pintype "input"))
      (node (ref "C22") (pin "1") (pinfunction "1_1") (pintype "input"))
      (node (ref "C23") (pin "1") (pinfunction "1_1") (pintype "input"))
      (node (ref "C24") (pin "2") (pinfunction "2_2") (pintype "input"))
      (node (ref "C25") (pin "2") (pinfunction "2_2") (pintype "input"))
      (node (ref "C26") (pin "1") (pinfunction "1_1") (pintype "input"))
      (node (ref "C27") (pin "1") (pinfunction "1_1") (pintype "input"))
      (node (ref "C28") (pin "1") (pinfunction "1_1") (pintype "input"))
      (node (ref "C29") (pin "1") (pinfunction "1_1") (pintype "input"))
      (node (ref "C3") (pin "1") (pinfunction "1_1") (pintype "input"))
      (node (ref "C30") (pin "2") (pinfunction "2_2") (pintype "input"))
      (node (ref "C4") (pin "1") (pinfunction "1_1") (pintype "input"))
      (node (ref "C5") (pin "1") (pinfunction "1_1") (pintype "input"))
      (node (ref "C6") (pin "1") (pinfunction "1_1") (pintype "input"))
      (node (ref "C7") (pin "1") (pinfunction "1_1") (pintype "input"))
      (node (ref "C8") (pin "1") (pinfunction "1_1") (pintype "input"))
      (node (ref "C9") (pin "1") (pinfunction "1_1") (pintype "input"))
      (node (ref "H1") (pin "10") (pinfunction "10_10") (pintype "unspecified"))
      (node (ref "H1") (pin "12") (pinfunction "12_12") (pintype "unspecified"))
      (node (ref "H1") (pin "3") (pinfunction "3_3") (pintype "unspecified"))
      (node (ref "H1") (pin "4") (pinfunction "4_4") (pintype "unspecified"))
      (node (ref "H1") (pin "6") (pinfunction "6_6") (pintype "unspecified"))
      (node (ref "H1") (pin "8") (pinfunction "8_8") (pintype "unspecified"))
      (node (ref "L1") (pin "3") (pinfunction "GND_3") (pintype "input"))
      (node (ref "L1") (pin "4") (pinfunction "NC_4") (pintype "input"))
      (node (ref "Q1") (pin "1") (pinfunction "S1_1") (pintype "unspecified"))
      (node (ref "Q1") (pin "4") (pinfunction "S2_4") (pintype "unspecified"))
      (node (ref "R1") (pin "1") (pinfunction "1_1") (pintype "input"))
      (node (ref "R14") (pin "1") (pinfunction "1_1") (pintype "input"))
      (node (ref "R2") (pin "1") (pinfunction "1_1") (pintype "input"))
      (node (ref "R21") (pin "1") (pinfunction "1_1") (pintype "input"))
      (node (ref "R3") (pin "1") (pinfunction "1_1") (pintype "input"))
      (node (ref "R5") (pin "1") (pinfunction "1_1") (pintype "input"))
      (node (ref "R6") (pin "2") (pinfunction "2_2") (pintype "input"))
      (node (ref "R8") (pin "2") (pinfunction "2_2") (pintype "input"))
      (node (ref "SW1") (pin "1") (pinfunction "1_1") (pintype "unspecified"))
      (node (ref "SW1") (pin "2") (pinfunction "2_2") (pintype "unspecified"))
      (node (ref "SW1") (pin "3") (pinfunction "3_3") (pintype "unspecified"))
      (node (ref "SW1") (pin "4") (pinfunction "4_4") (pintype "unspecified"))
      (node (ref "SW1") (pin "5") (pinfunction "5_5") (pintype "unspecified"))
      (node (ref "U1") (pin "1") (pinfunction "1_1") (pintype "input"))
      (node (ref "U1") (pin "11") (pinfunction "11_11") (pintype "input"))
      (node (ref "U1") (pin "13") (pinfunction "13_13") (pintype "input"))
      (node (ref "U1") (pin "3") (pinfunction "3_3") (pintype "input"))
      (node (ref "U1") (pin "5") (pinfunction "5_5") (pintype "input"))
      (node (ref "U1") (pin "7") (pinfunction "7_7") (pintype "input"))
      (node (ref "U1") (pin "9") (pinfunction "9_9") (pintype "input"))
      (node (ref "U10") (pin "11") (pinfunction "GND_11") (pintype "unspecified"))
      (node (ref "U11") (pin "18") (pinfunction "GND_18") (pintype "input"))
      (node (ref "U11") (pin "21") (pinfunction "EP_21") (pintype "input"))
      (node (ref "U11") (pin "8") (pinfunction "GND_8") (pintype "input"))
      (node (ref "U12") (pin "1") (pinfunction "1_1") (pintype "input"))
      (node (ref "U13") (pin "1") (pinfunction "1_1") (pintype "input"))
      (node (ref "U14") (pin "1") (pinfunction "1_1") (pintype "input"))
      (node (ref "U15") (pin "1") (pinfunction "1_1") (pintype "input"))
      (node (ref "U16") (pin "1") (pinfunction "GND_1") (pintype "unspecified"))
      (node (ref "U17") (pin "1") (pinfunction "1_1") (pintype "input"))
      (node (ref "U17") (pin "11") (pinfunction "11_11") (pintype "input"))
      (node (ref "U17") (pin "13") (pinfunction "13_13") (pintype "input"))
      (node (ref "U17") (pin "3") (pinfunction "3_3") (pintype "input"))
      (node (ref "U17") (pin "5") (pinfunction "5_5") (pintype "input"))
      (node (ref "U17") (pin "7") (pinfunction "7_7") (pintype "input"))
      (node (ref "U17") (pin "9") (pinfunction "9_9") (pintype "input"))
      (node (ref "U18") (pin "1") (pinfunction "1_1") (pintype "input"))
      (node (ref "U18") (pin "11") (pinfunction "11_11") (pintype "input"))
      (node (ref "U18") (pin "12") (pinfunction "12_12") (pintype "input"))
      (node (ref "U18") (pin "13") (pinfunction "13_13") (pintype "input"))
      (node (ref "U18") (pin "14") (pinfunction "14_14") (pintype "input"))
      (node (ref "U18") (pin "3") (pinfunction "3_3") (pintype "input"))
      (node (ref "U18") (pin "5") (pinfunction "5_5") (pintype "input"))
      (node (ref "U18") (pin "7") (pinfunction "7_7") (pintype "input"))
      (node (ref "U18") (pin "9") (pinfunction "9_9") (pintype "input"))
      (node (ref "U19") (pin "1") (pinfunction "1_1") (pintype "input"))
      (node (ref "U19") (pin "11") (pinfunction "11_11") (pintype "input"))
      (node (ref "U19") (pin "12") (pinfunction "12_12") (pintype "input"))
      (node (ref "U19") (pin "13") (pinfunction "13_13") (pintype "input"))
      (node (ref "U19") (pin "14") (pinfunction "14_14") (pintype "input"))
      (node (ref "U19") (pin "3") (pinfunction "3_3") (pintype "input"))
      (node (ref "U19") (pin "5") (pinfunction "5_5") (pintype "input"))
      (node (ref "U19") (pin "7") (pinfunction "7_7") (pintype "input"))
      (node (ref "U19") (pin "9") (pinfunction "9_9") (pintype "input"))
      (node (ref "U2") (pin "1") (pinfunction "GND_1") (pintype "input"))
      (node (ref "U2") (pin "10") (pinfunction "AGND_10") (pintype "input"))
      (node (ref "U2") (pin "11") (pinfunction "GND_11") (pintype "input"))
      (node (ref "U2") (pin "13") (pinfunction "TEST_13") (pintype "input"))
      (node (ref "U2") (pin "15") (pinfunction "GND_15") (pintype "input"))
      (node (ref "U2") (pin "25") (pinfunction "GND_25") (pintype "input"))
      (node (ref "U2") (pin "35") (pinfunction "GND_35") (pintype "input"))
      (node (ref "U2") (pin "47") (pinfunction "GND_47") (pintype "input"))
      (node (ref "U2") (pin "5") (pinfunction "GND_5") (pintype "input"))
      (node (ref "U2") (pin "51") (pinfunction "GND_51") (pintype "input"))
      (node (ref "U2") (pin "65") (pinfunction "EP_65") (pintype "input"))
      (node (ref "U20") (pin "4") (pinfunction "4_4") (pintype "input"))
      (node (ref "U21") (pin "4") (pinfunction "4_4") (pintype "input"))
      (node (ref "U3") (pin "4") (pinfunction "4_4") (pintype "input"))
      (node (ref "U4") (pin "5") (pinfunction "GND_5") (pintype "input"))
      (node (ref "U4") (pin "7") (pinfunction "EP_7") (pintype "input"))
      (node (ref "U5") (pin "2") (pinfunction "GND_2") (pintype "input"))
      (node (ref "U6") (pin "2") (pinfunction "VSS_2") (pintype "input"))
      (node (ref "U7") (pin "2") (pinfunction "GND_2") (pintype "unspecified"))
      (node (ref "U8") (pin "3") (pinfunction "GND_3") (pintype "unspecified"))
      (node (ref "U9") (pin "2") (pinfunction "GND_2") (pintype "unspecified"))
      (node (ref "USB1") (pin "1") (pinfunction "GND_1") (pintype "unspecified"))
      (node (ref "USB1") (pin "12") (pinfunction "GND_12") (pintype "unspecified"))
      (node (ref "USB1") (pin "13") (pinfunction "SHELL_13") (pintype "unspecified"))
      (node (ref "USB1") (pin "14") (pinfunction "SHELL_14") (pintype "unspecified"))
      (node (ref "USB1") (pin "15") (pinfunction "SHELL_15") (pintype "unspecified"))
      (node (ref "USB1") (pin "16") (pinfunction "SHELL_16") (pintype "unspecified"))
      (node (ref "X1") (pin "2") (pinfunction "GND_2") (pintype "unspecified"))
    )
    (net (code "14") (name "INT_VERF") (class "Default")
      (node (ref "C25") (pin "1") (pinfunction "1_1") (pintype "input"))
      (node (ref "C31") (pin "1") (pinfunction "1_1") (pintype "input"))
      (node (ref "U11") (pin "1") (pinfunction "OUT_1") (pintype "input"))
      (node (ref "U11") (pin "19") (pinfunction "OUT_19") (pintype "input"))
      (node (ref "U11") (pin "2") (pinfunction "SNS_2") (pintype "input"))
      (node (ref "U11") (pin "20") (pinfunction "OUT_20") (pintype "input"))
      (node (ref "U16") (pin "6") (pinfunction "VIN2_6") (pintype "unspecified"))
    )
    (net (code "15") (name "JTAG_TCK") (class "Default")
      (node (ref "U10") (pin "5") (pinfunction "A4_5") (pintype "unspecified"))
      (node (ref "U2") (pin "16") (pinfunction "ADBUS0_16") (pintype "input"))
    )
    (net (code "16") (name "JTAG_TCK_O") (class "Default")
      (node (ref "U1") (pin "6") (pinfunction "6_6") (pintype "input"))
      (node (ref "U10") (pin "16") (pinfunction "B4_16") (pintype "unspecified"))
    )
    (net (code "17") (name "JTAG_TDI") (class "Default")
      (node (ref "U10") (pin "6") (pinfunction "A5_6") (pintype "unspecified"))
      (node (ref "U2") (pin "17") (pinfunction "ADBUS1_17") (pintype "input"))
    )
    (net (code "18") (name "JTAG_TDI_O") (class "Default")
      (node (ref "U1") (pin "10") (pinfunction "10_10") (pintype "input"))
      (node (ref "U10") (pin "15") (pinfunction "B5_15") (pintype "unspecified"))
    )
    (net (code "19") (name "JTAG_TDO") (class "Default")
      (node (ref "U10") (pin "7") (pinfunction "A6_7") (pintype "unspecified"))
      (node (ref "U2") (pin "18") (pinfunction "ADBUS2_18") (pintype "input"))
    )
    (net (code "20") (name "JTAG_TDO_O") (class "Default")
      (node (ref "U1") (pin "8") (pinfunction "8_8") (pintype "input"))
      (node (ref "U10") (pin "14") (pinfunction "B6_14") (pintype "unspecified"))
    )
    (net (code "21") (name "JTAG_TMS") (class "Default")
      (node (ref "U10") (pin "8") (pinfunction "A7_8") (pintype "unspecified"))
      (node (ref "U2") (pin "19") (pinfunction "ADBUS3_19") (pintype "input"))
    )
    (net (code "22") (name "JTAG_TMS_O") (class "Default")
      (node (ref "U1") (pin "4") (pinfunction "4_4") (pintype "input"))
      (node (ref "U10") (pin "13") (pinfunction "B7_13") (pintype "unspecified"))
    )
    (net (code "23") (name "JTAG_VREF") (class "Default")
      (node (ref "U1") (pin "2") (pinfunction "2_2") (pintype "input"))
      (node (ref "U16") (pin "3") (pinfunction "VIN1_3") (pintype "unspecified"))
    )
    (net (code "24") (name "MR#{slash}A") (class "Default")
      (node (ref "TP10") (pin "1") (pinfunction "1_1") (pintype "input"))
      (node (ref "U9") (pin "3") (pinfunction "MR#_3") (pintype "unspecified"))
    )
    (net (code "25") (name "MR#{slash}B") (class "Default")
      (node (ref "TP11") (pin "1") (pinfunction "1_1") (pintype "input"))
      (node (ref "U7") (pin "3") (pinfunction "MR#_3") (pintype "unspecified"))
    )
    (net (code "26") (name "Net-(C15-IN)") (class "Default")
      (node (ref "C12") (pin "1") (pinfunction "1_1") (pintype "input"))
      (node (ref "C15") (pin "1") (pinfunction "IN_1") (pintype "input"))
      (node (ref "U5") (pin "1") (pinfunction "IN_1") (pintype "input"))
    )
    (net (code "27") (name "Net-(LED1-C)") (class "Default")
      (node (ref "LED1") (pin "1") (pinfunction "C_1") (pintype "input"))
      (node (ref "R3") (pin "2") (pinfunction "2_2") (pintype "input"))
    )
    (net (code "28") (name "Net-(LED2-A)") (class "Default")
      (node (ref "LED2") (pin "2") (pinfunction "A_2") (pintype "input"))
      (node (ref "R4") (pin "1") (pinfunction "1_1") (pintype "input"))
    )
    (net (code "29") (name "Net-(LED2-C)") (class "Default")
      (node (ref "LED2") (pin "1") (pinfunction "C_1") (pintype "input"))
      (node (ref "Q1") (pin "6") (pinfunction "D1_6") (pintype "unspecified"))
    )
    (net (code "30") (name "Net-(LED3-A)") (class "Default")
      (node (ref "LED3") (pin "2") (pinfunction "A_2") (pintype "input"))
      (node (ref "R13") (pin "2") (pinfunction "2_2") (pintype "input"))
    )
    (net (code "31") (name "Net-(LED3-C)") (class "Default")
      (node (ref "LED3") (pin "1") (pinfunction "C_1") (pintype "input"))
      (node (ref "Q1") (pin "3") (pinfunction "D2_3") (pintype "unspecified"))
    )
    (net (code "32") (name "Net-(Q1-G1)") (class "Default")
      (node (ref "Q1") (pin "2") (pinfunction "G1_2") (pintype "unspecified"))
      (node (ref "R5") (pin "2") (pinfunction "2_2") (pintype "input"))
      (node (ref "R7") (pin "1") (pinfunction "1_1") (pintype "input"))
    )
    (net (code "33") (name "Net-(Q1-G2)") (class "Default")
      (node (ref "Q1") (pin "5") (pinfunction "G2_5") (pintype "unspecified"))
      (node (ref "R8") (pin "1") (pinfunction "1_1") (pintype "input"))
      (node (ref "R9") (pin "2") (pinfunction "2_2") (pintype "input"))
    )
    (net (code "34") (name "Net-(U2-REF)") (class "Default")
      (node (ref "R14") (pin "2") (pinfunction "2_2") (pintype "input"))
      (node (ref "U2") (pin "6") (pinfunction "REF_6") (pintype "input"))
    )
    (net (code "35") (name "Net-(U2-RESET#)") (class "Default")
      (node (ref "R15") (pin "2") (pinfunction "2_2") (pintype "input"))
      (node (ref "U2") (pin "14") (pinfunction "RESET#_14") (pintype "input"))
    )
    (net (code "36") (name "Net-(U2-VPHY)") (class "Default")
      (node (ref "L3") (pin "2") (pinfunction "2_2") (pintype "input"))
      (node (ref "U2") (pin "4") (pinfunction "VPHY_4") (pintype "input"))
    )
    (net (code "37") (name "Net-(U2-VPLL)") (class "Default")
      (node (ref "L2") (pin "1") (pinfunction "1_1") (pintype "input"))
      (node (ref "U2") (pin "9") (pinfunction "VPLL_9") (pintype "input"))
    )
    (net (code "38") (name "Net-(U4-EN)") (class "Default")
      (node (ref "R12") (pin "1") (pinfunction "1_1") (pintype "input"))
      (node (ref "U4") (pin "4") (pinfunction "EN_4") (pintype "input"))
    )
    (net (code "39") (name "Net-(U4-ILIM)") (class "Default")
      (node (ref "R6") (pin "1") (pinfunction "1_1") (pintype "input"))
      (node (ref "U4") (pin "2") (pinfunction "ILIM_2") (pintype "input"))
    )
    (net (code "40") (name "Net-(U7-CT)") (class "Default")
      (node (ref "C22") (pin "2") (pinfunction "2_2") (pintype "input"))
      (node (ref "U7") (pin "4") (pinfunction "CT_4") (pintype "unspecified"))
    )
    (net (code "41") (name "Net-(U9-CT)") (class "Default")
      (node (ref "C21") (pin "2") (pinfunction "2_2") (pintype "input"))
      (node (ref "U9") (pin "4") (pinfunction "CT_4") (pintype "unspecified"))
    )
    (net (code "42") (name "Net-(U11-FB)") (class "Default")
      (node (ref "C31") (pin "2") (pinfunction "2_2") (pintype "input"))
      (node (ref "U11") (pin "3") (pinfunction "FB_3") (pintype "input"))
    )
    (net (code "43") (name "Net-(U11-NR{slash}SS)") (class "Default")
      (node (ref "C30") (pin "1") (pinfunction "1_1") (pintype "input"))
      (node (ref "U11") (pin "13") (pinfunction "NR/SS_13") (pintype "input"))
    )
    (net (code "44") (name "Net-(U16-MODE)") (class "Default")
      (node (ref "R20") (pin "2") (pinfunction "2_2") (pintype "input"))
      (node (ref "U16") (pin "5") (pinfunction "MODE_5") (pintype "unspecified"))
    )
    (net (code "45") (name "OSCI") (class "Default")
      (node (ref "U2") (pin "2") (pinfunction "OSCI_2") (pintype "input"))
      (node (ref "X1") (pin "1") (pinfunction "INPUT_1") (pintype "unspecified"))
    )
    (net (code "46") (name "OSCO") (class "Default")
      (node (ref "TP13") (pin "1") (pinfunction "1_1") (pintype "input"))
      (node (ref "U2") (pin "3") (pinfunction "OSCO_3") (pintype "input"))
      (node (ref "X1") (pin "3") (pinfunction "OUTPUT_3") (pintype "unspecified"))
    )
    (net (code "47") (name "RESET#{slash}OE{slash}A") (class "Default")
      (node (ref "R16") (pin "2") (pinfunction "2_2") (pintype "input"))
      (node (ref "TP7") (pin "1") (pinfunction "1_1") (pintype "input"))
      (node (ref "U8") (pin "1") (pinfunction "A_1") (pintype "unspecified"))
      (node (ref "U9") (pin "1") (pinfunction "RESET#_1") (pintype "unspecified"))
    )
    (net (code "48") (name "RESET#{slash}OE{slash}B") (class "Default")
      (node (ref "R17") (pin "2") (pinfunction "2_2") (pintype "input"))
      (node (ref "TP8") (pin "1") (pinfunction "1_1") (pintype "input"))
      (node (ref "U7") (pin "1") (pinfunction "RESET#_1") (pintype "unspecified"))
      (node (ref "U8") (pin "2") (pinfunction "B_2") (pintype "unspecified"))
    )
    (net (code "49") (name "RESET#{slash}OE{slash}Y") (class "Default")
      (node (ref "TP12") (pin "1") (pinfunction "1_1") (pintype "input"))
      (node (ref "U10") (pin "10") (pinfunction "OE_10") (pintype "unspecified"))
      (node (ref "U8") (pin "4") (pinfunction "Y_4") (pintype "unspecified"))
    )
    (net (code "50") (name "TCK_CONN") (class "Default")
      (node (ref "H1") (pin "5") (pinfunction "5_5") (pintype "unspecified"))
      (node (ref "U17") (pin "10") (pinfunction "10_10") (pintype "input"))
      (node (ref "U18") (pin "10") (pinfunction "10_10") (pintype "input"))
      (node (ref "U19") (pin "10") (pinfunction "10_10") (pintype "input"))
    )
    (net (code "51") (name "TDI_CONN") (class "Default")
      (node (ref "H1") (pin "9") (pinfunction "9_9") (pintype "unspecified"))
      (node (ref "U17") (pin "6") (pinfunction "6_6") (pintype "input"))
      (node (ref "U18") (pin "6") (pinfunction "6_6") (pintype "input"))
      (node (ref "U19") (pin "6") (pinfunction "6_6") (pintype "input"))
    )
    (net (code "52") (name "TDO_CONN") (class "Default")
      (node (ref "H1") (pin "7") (pinfunction "7_7") (pintype "unspecified"))
      (node (ref "U17") (pin "8") (pinfunction "8_8") (pintype "input"))
      (node (ref "U18") (pin "8") (pinfunction "8_8") (pintype "input"))
      (node (ref "U19") (pin "8") (pinfunction "8_8") (pintype "input"))
    )
    (net (code "53") (name "TMS_CONN") (class "Default")
      (node (ref "H1") (pin "11") (pinfunction "11_11") (pintype "unspecified"))
      (node (ref "U17") (pin "4") (pinfunction "4_4") (pintype "input"))
      (node (ref "U18") (pin "4") (pinfunction "4_4") (pintype "input"))
      (node (ref "U19") (pin "4") (pinfunction "4_4") (pintype "input"))
    )
    (net (code "54") (name "UART_RXD") (class "Default")
      (node (ref "R9") (pin "1") (pinfunction "1_1") (pintype "input"))
      (node (ref "U10") (pin "4") (pinfunction "A3_4") (pintype "unspecified"))
      (node (ref "U2") (pin "39") (pinfunction "BDBUS1_39") (pintype "input"))
    )
    (net (code "55") (name "UART_RXD_CONN") (class "Default")
      (node (ref "U20") (pin "1") (pinfunction "1_1") (pintype "input"))
      (node (ref "U21") (pin "1") (pinfunction "1_1") (pintype "input"))
    )
    (net (code "56") (name "UART_RXD_O") (class "Default")
      (node (ref "U10") (pin "17") (pinfunction "B3_17") (pintype "unspecified"))
      (node (ref "U3") (pin "1") (pinfunction "1_1") (pintype "input"))
    )
    (net (code "57") (name "UART_TXD") (class "Default")
      (node (ref "R7") (pin "2") (pinfunction "2_2") (pintype "input"))
      (node (ref "U10") (pin "3") (pinfunction "A2_3") (pintype "unspecified"))
      (node (ref "U2") (pin "38") (pinfunction "BDBUS0_38") (pintype "input"))
    )
    (net (code "58") (name "UART_TXD_CONN") (class "Default")
      (node (ref "U20") (pin "2") (pinfunction "2_2") (pintype "input"))
      (node (ref "U21") (pin "2") (pinfunction "2_2") (pintype "input"))
    )
    (net (code "59") (name "UART_TXD_O") (class "Default")
      (node (ref "U10") (pin "18") (pinfunction "B2_18") (pintype "unspecified"))
      (node (ref "U3") (pin "2") (pinfunction "2_2") (pintype "input"))
    )
    (net (code "60") (name "USB_5V") (class "Default")
      (node (ref "C17") (pin "2") (pinfunction "2_2") (pintype "input"))
      (node (ref "R12") (pin "2") (pinfunction "2_2") (pintype "input"))
      (node (ref "TP2") (pin "1") (pinfunction "1_1") (pintype "input"))
      (node (ref "U4") (pin "6") (pinfunction "IN_6") (pintype "input"))
      (node (ref "USB1") (pin "11") (pinfunction "VBUS_11") (pintype "unspecified"))
      (node (ref "USB1") (pin "2") (pinfunction "VBUS_2") (pintype "unspecified"))
    )
    (net (code "61") (name "USB_CC1") (class "Default")
      (node (ref "R2") (pin "2") (pinfunction "2_2") (pintype "input"))
      (node (ref "USB1") (pin "4") (pinfunction "CC1_4") (pintype "unspecified"))
    )
    (net (code "62") (name "USB_CC2") (class "Default")
      (node (ref "R1") (pin "2") (pinfunction "2_2") (pintype "input"))
      (node (ref "USB1") (pin "10") (pinfunction "CC2_10") (pintype "unspecified"))
    )
    (net (code "63") (name "USB_DN") (class "Default")
      (node (ref "L1") (pin "5") (pinfunction "D-_5") (pintype "input"))
      (node (ref "USB1") (pin "5") (pinfunction "DN2_5") (pintype "unspecified"))
      (node (ref "USB1") (pin "7") (pinfunction "DN1_7") (pintype "unspecified"))
    )
    (net (code "64") (name "USB_DN_O") (class "Default")
      (node (ref "L1") (pin "2") (pinfunction "D-_2") (pintype "input"))
      (node (ref "U2") (pin "7") (pinfunction "DM_7") (pintype "input"))
    )
    (net (code "65") (name "USB_DP") (class "Default")
      (node (ref "L1") (pin "6") (pinfunction "D+_6") (pintype "input"))
      (node (ref "USB1") (pin "6") (pinfunction "DP1_6") (pintype "unspecified"))
      (node (ref "USB1") (pin "8") (pinfunction "DP2_8") (pintype "unspecified"))
    )
    (net (code "66") (name "USB_DP_O") (class "Default")
      (node (ref "L1") (pin "1") (pinfunction "D+_1") (pintype "input"))
      (node (ref "U2") (pin "8") (pinfunction "DP_8") (pintype "input"))
    )
    (net (code "67") (name "VCCB") (class "Default")
      (node (ref "C19") (pin "2") (pinfunction "2_2") (pintype "input"))
      (node (ref "C28") (pin "2") (pinfunction "2_2") (pintype "input"))
      (node (ref "C29") (pin "2") (pinfunction "2_2") (pintype "input"))
      (node (ref "R17") (pin "1") (pinfunction "1_1") (pintype "input"))
      (node (ref "U10") (pin "19") (pinfunction "VCCB_19") (pintype "unspecified"))
      (node (ref "U16") (pin "2") (pinfunction "VOUT_2") (pintype "unspecified"))
      (node (ref "U16") (pin "7") (pinfunction "VOUT_7") (pintype "unspecified"))
      (node (ref "U7") (pin "5") (pinfunction "SENSE_5") (pintype "unspecified"))
      (node (ref "U7") (pin "6") (pinfunction "VDD_6") (pintype "unspecified"))
    )
    (net (code "68") (name "VCORE") (class "Default")
      (node (ref "C10") (pin "2") (pinfunction "2_2") (pintype "input"))
      (node (ref "C11") (pin "2") (pinfunction "2_2") (pintype "input"))
      (node (ref "C13") (pin "1") (pinfunction "1_1") (pintype "input"))
      (node (ref "C9") (pin "2") (pinfunction "2_2") (pintype "input"))
      (node (ref "TP1") (pin "1") (pinfunction "1_1") (pintype "input"))
      (node (ref "U2") (pin "12") (pinfunction "VCORE_12") (pintype "input"))
      (node (ref "U2") (pin "37") (pinfunction "VCORE_37") (pintype "input"))
      (node (ref "U2") (pin "49") (pinfunction "VREGOUT_49") (pintype "input"))
      (node (ref "U2") (pin "64") (pinfunction "VCORE_64") (pintype "input"))
    )
    (net (code "69") (name "VREF_CONN") (class "Default")
      (node (ref "H1") (pin "1") (pinfunction "1_1") (pintype "unspecified"))
      (node (ref "H1") (pin "2") (pinfunction "2_2") (pintype "unspecified"))
      (node (ref "U17") (pin "2") (pinfunction "2_2") (pintype "input"))
      (node (ref "U18") (pin "2") (pinfunction "2_2") (pintype "input"))
      (node (ref "U19") (pin "2") (pinfunction "2_2") (pintype "input"))
    )
    (net (code "70") (name "VREF_SEL") (class "Default")
      (node (ref "R21") (pin "2") (pinfunction "2_2") (pintype "input"))
      (node (ref "SW1") (pin "7") (pinfunction "7_7") (pintype "unspecified"))
      (node (ref "U16") (pin "4") (pinfunction "PR1_4") (pintype "unspecified"))
    )
    (net (code "71") (name "unconnected-(U1-Pad12)") (class "Default")
      (node (ref "U1") (pin "12") (pinfunction "12_12") (pintype "input+no_connect"))
    )
    (net (code "72") (name "unconnected-(U1-Pad14)") (class "Default")
      (node (ref "U1") (pin "14") (pinfunction "14_14") (pintype "input+no_connect"))
    )
    (net (code "73") (name "unconnected-(U2-ACBUS0-Pad26)") (class "Default")
      (node (ref "U2") (pin "26") (pinfunction "ACBUS0_26") (pintype "input+no_connect"))
    )
    (net (code "74") (name "unconnected-(U2-ACBUS1-Pad27)") (class "Default")
      (node (ref "U2") (pin "27") (pinfunction "ACBUS1_27") (pintype "input+no_connect"))
    )
    (net (code "75") (name "unconnected-(U2-ACBUS2-Pad28)") (class "Default")
      (node (ref "U2") (pin "28") (pinfunction "ACBUS2_28") (pintype "input+no_connect"))
    )
    (net (code "76") (name "unconnected-(U2-ACBUS3-Pad29)") (class "Default")
      (node (ref "U2") (pin "29") (pinfunction "ACBUS3_29") (pintype "input+no_connect"))
    )
    (net (code "77") (name "unconnected-(U2-ACBUS4-Pad30)") (class "Default")
      (node (ref "U2") (pin "30") (pinfunction "ACBUS4_30") (pintype "input+no_connect"))
    )
    (net (code "78") (name "unconnected-(U2-ACBUS5-Pad32)") (class "Default")
      (node (ref "U2") (pin "32") (pinfunction "ACBUS5_32") (pintype "input+no_connect"))
    )
    (net (code "79") (name "unconnected-(U2-ACBUS6-Pad33)") (class "Default")
      (node (ref "U2") (pin "33") (pinfunction "ACBUS6_33") (pintype "input+no_connect"))
    )
    (net (code "80") (name "unconnected-(U2-ACBUS7-Pad34)") (class "Default")
      (node (ref "U2") (pin "34") (pinfunction "ACBUS7_34") (pintype "input+no_connect"))
    )
    (net (code "81") (name "unconnected-(U2-ADBUS4-Pad21)") (class "Default")
      (node (ref "U2") (pin "21") (pinfunction "ADBUS4_21") (pintype "input+no_connect"))
    )
    (net (code "82") (name "unconnected-(U2-ADBUS5-Pad22)") (class "Default")
      (node (ref "U2") (pin "22") (pinfunction "ADBUS5_22") (pintype "input+no_connect"))
    )
    (net (code "83") (name "unconnected-(U2-ADBUS6-Pad23)") (class "Default")
      (node (ref "U2") (pin "23") (pinfunction "ADBUS6_23") (pintype "input+no_connect"))
    )
    (net (code "84") (name "unconnected-(U2-ADBUS7-Pad24)") (class "Default")
      (node (ref "U2") (pin "24") (pinfunction "ADBUS7_24") (pintype "input+no_connect"))
    )
    (net (code "85") (name "unconnected-(U2-BCBUS0-Pad48)") (class "Default")
      (node (ref "U2") (pin "48") (pinfunction "BCBUS0_48") (pintype "input+no_connect"))
    )
    (net (code "86") (name "unconnected-(U2-BCBUS1-Pad52)") (class "Default")
      (node (ref "U2") (pin "52") (pinfunction "BCBUS1_52") (pintype "input+no_connect"))
    )
    (net (code "87") (name "unconnected-(U2-BCBUS2-Pad53)") (class "Default")
      (node (ref "U2") (pin "53") (pinfunction "BCBUS2_53") (pintype "input+no_connect"))
    )
    (net (code "88") (name "unconnected-(U2-BCBUS3-Pad54)") (class "Default")
      (node (ref "U2") (pin "54") (pinfunction "BCBUS3_54") (pintype "input+no_connect"))
    )
    (net (code "89") (name "unconnected-(U2-BCBUS4-Pad55)") (class "Default")
      (node (ref "U2") (pin "55") (pinfunction "BCBUS4_55") (pintype "input+no_connect"))
    )
    (net (code "90") (name "unconnected-(U2-BCBUS5-Pad57)") (class "Default")
      (node (ref "U2") (pin "57") (pinfunction "BCBUS5_57") (pintype "input+no_connect"))
    )
    (net (code "91") (name "unconnected-(U2-BCBUS6-Pad58)") (class "Default")
      (node (ref "U2") (pin "58") (pinfunction "BCBUS6_58") (pintype "input+no_connect"))
    )
    (net (code "92") (name "unconnected-(U2-BCBUS7-Pad59)") (class "Default")
      (node (ref "U2") (pin "59") (pinfunction "BCBUS7_59") (pintype "input+no_connect"))
    )
    (net (code "93") (name "unconnected-(U2-BDBUS2-Pad40)") (class "Default")
      (node (ref "U2") (pin "40") (pinfunction "BDBUS2_40") (pintype "input+no_connect"))
    )
    (net (code "94") (name "unconnected-(U2-BDBUS3-Pad41)") (class "Default")
      (node (ref "U2") (pin "41") (pinfunction "BDBUS3_41") (pintype "input+no_connect"))
    )
    (net (code "95") (name "unconnected-(U2-BDBUS4-Pad43)") (class "Default")
      (node (ref "U2") (pin "43") (pinfunction "BDBUS4_43") (pintype "input+no_connect"))
    )
    (net (code "96") (name "unconnected-(U2-BDBUS5-Pad44)") (class "Default")
      (node (ref "U2") (pin "44") (pinfunction "BDBUS5_44") (pintype "input+no_connect"))
    )
    (net (code "97") (name "unconnected-(U2-BDBUS6-Pad45)") (class "Default")
      (node (ref "U2") (pin "45") (pinfunction "BDBUS6_45") (pintype "input+no_connect"))
    )
    (net (code "98") (name "unconnected-(U2-BDBUS7-Pad46)") (class "Default")
      (node (ref "U2") (pin "46") (pinfunction "BDBUS7_46") (pintype "input+no_connect"))
    )
    (net (code "99") (name "unconnected-(U2-PWREN#-Pad60)") (class "Default")
      (node (ref "U2") (pin "60") (pinfunction "PWREN#_60") (pintype "input+no_connect"))
    )
    (net (code "100") (name "unconnected-(U2-SUSPEND#-Pad36)") (class "Default")
      (node (ref "U2") (pin "36") (pinfunction "SUSPEND#_36") (pintype "input+no_connect"))
    )
    (net (code "101") (name "unconnected-(U4-FAULT#-Pad3)") (class "Default")
      (node (ref "U4") (pin "3") (pinfunction "FAULT#_3") (pintype "input+no_connect"))
    )
    (net (code "102") (name "unconnected-(U5-NC-Pad4)") (class "Default")
      (node (ref "U5") (pin "4") (pinfunction "NC_4") (pintype "input+no_connect"))
    )
    (net (code "103") (name "unconnected-(U10-A1-Pad1)") (class "Default")
      (node (ref "U10") (pin "1") (pinfunction "A1_1") (pintype "unspecified+no_connect"))
    )
    (net (code "104") (name "unconnected-(U10-A8-Pad9)") (class "Default")
      (node (ref "U10") (pin "9") (pinfunction "A8_9") (pintype "unspecified+no_connect"))
    )
    (net (code "105") (name "unconnected-(U10-B1-Pad20)") (class "Default")
      (node (ref "U10") (pin "20") (pinfunction "B1_20") (pintype "unspecified+no_connect"))
    )
    (net (code "106") (name "unconnected-(U10-B8-Pad12)") (class "Default")
      (node (ref "U10") (pin "12") (pinfunction "B8_12") (pintype "unspecified+no_connect"))
    )
    (net (code "107") (name "unconnected-(U11-50mV-Pad5)") (class "Default")
      (node (ref "U11") (pin "5") (pinfunction "50mV_5") (pintype "input+no_connect"))
    )
    (net (code "108") (name "unconnected-(U11-BIAS-Pad12)") (class "Default")
      (node (ref "U11") (pin "12") (pinfunction "BIAS_12") (pintype "input+no_connect"))
    )
    (net (code "109") (name "unconnected-(U11-PG-Pad4)") (class "Default")
      (node (ref "U11") (pin "4") (pinfunction "PG_4") (pintype "input+no_connect"))
    )
    (net (code "110") (name "unconnected-(U16-ST-Pad8)") (class "Default")
      (node (ref "U16") (pin "8") (pinfunction "ST_8") (pintype "unspecified+no_connect"))
    )
    (net (code "111") (name "unconnected-(U17-Pad12)") (class "Default")
      (node (ref "U17") (pin "12") (pinfunction "12_12") (pintype "input+no_connect"))
    )
    (net (code "112") (name "unconnected-(U17-Pad14)") (class "Default")
      (node (ref "U17") (pin "14") (pinfunction "14_14") (pintype "input+no_connect"))
    )
    (net (code "113") (name "unconnected-(USB1-SBU1-Pad9)") (class "Default")
      (node (ref "USB1") (pin "9") (pinfunction "SBU1_9") (pintype "unspecified+no_connect"))
    )
    (net (code "114") (name "unconnected-(USB1-SBU2-Pad3)") (class "Default")
      (node (ref "USB1") (pin "3") (pinfunction "SBU2_3") (pintype "unspecified+no_connect"))
    )
  )
)
